# BareBonesArduino.net
KiCad netlist of a schematic drawn in EAGLE
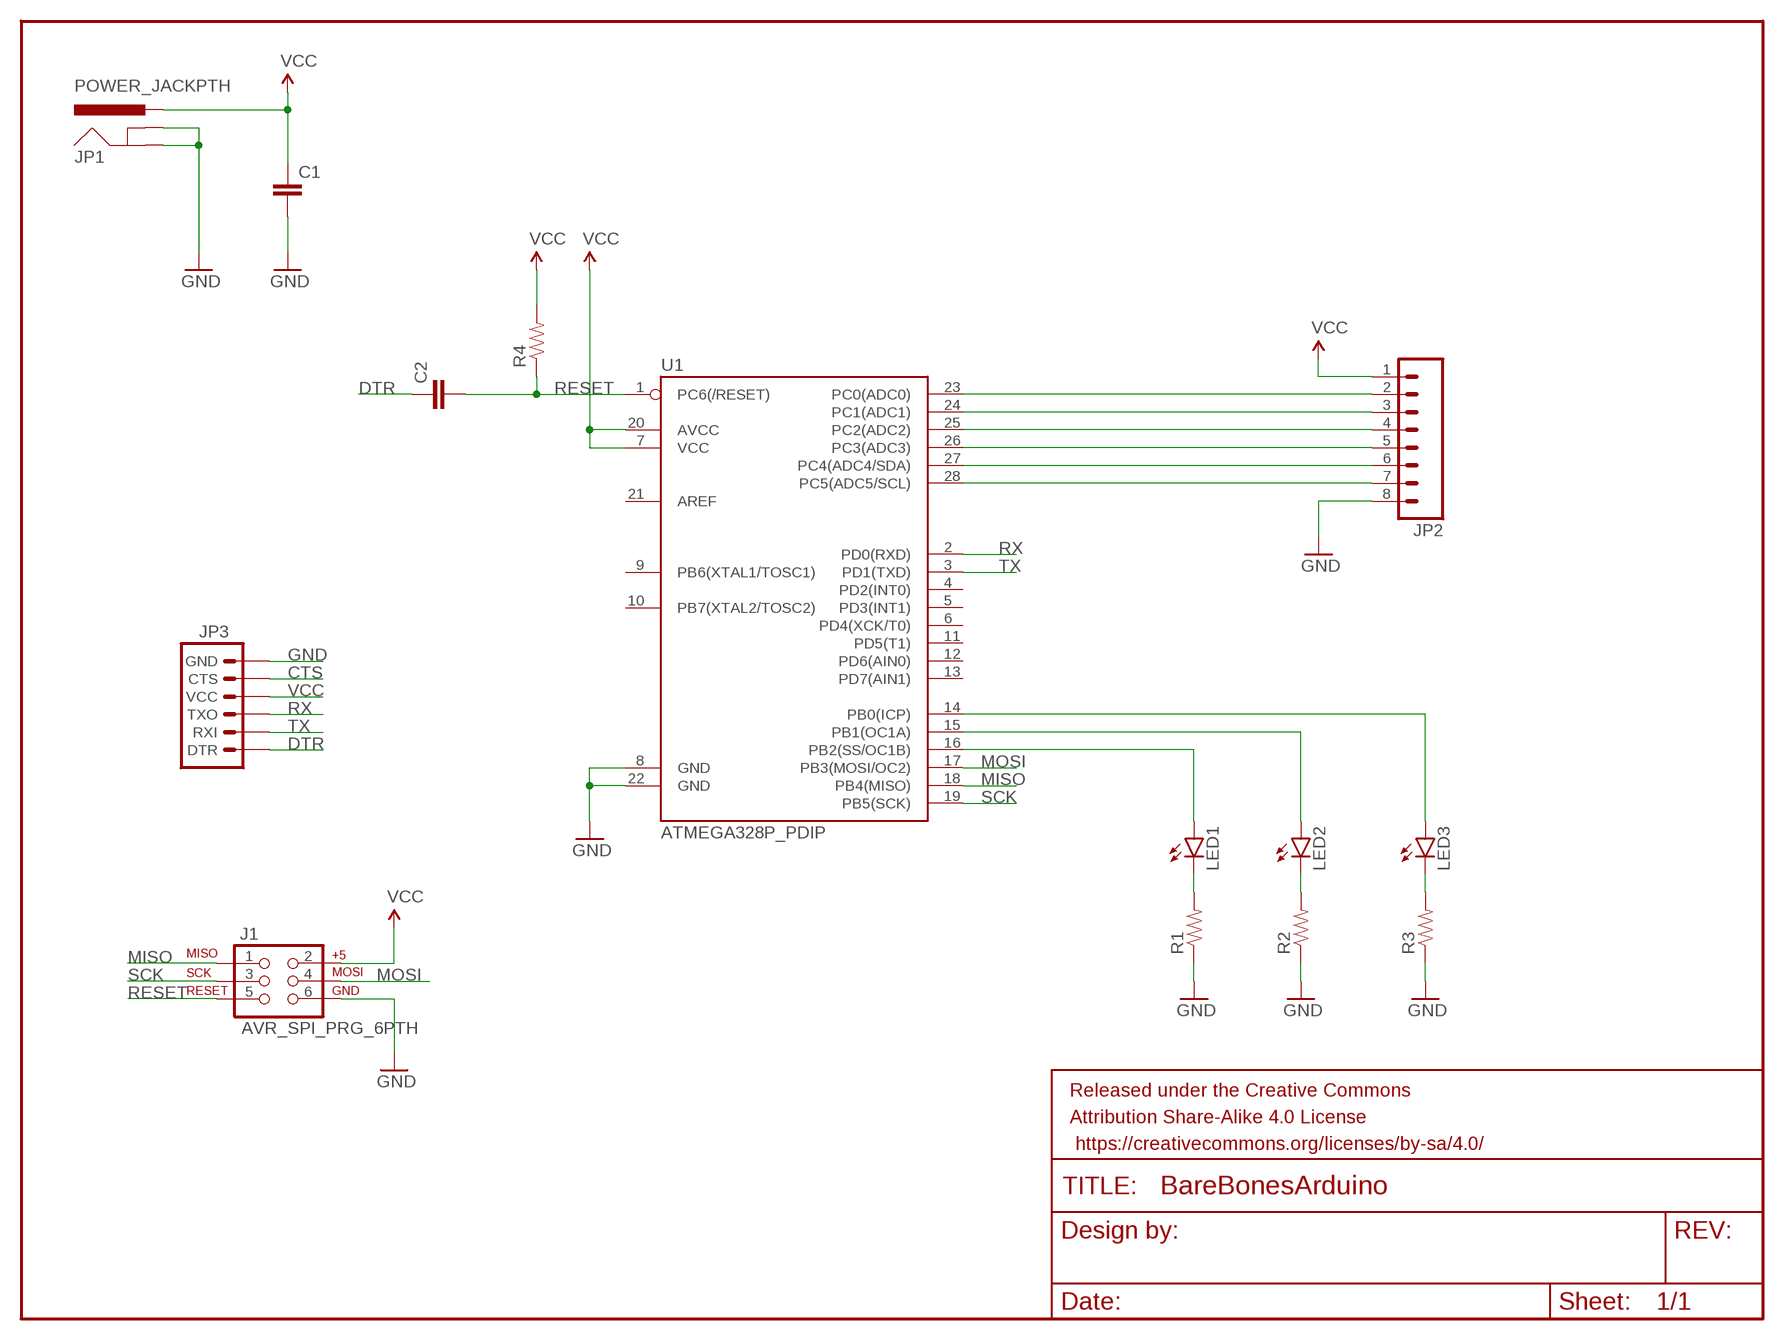
[diagram p0: schematic, sheet 1]

(export (version "E")
  (design (tool "Eeschema 10.0.6"))
  (components
    (comp (ref "C1")
      (value "CAPPTH")
      (footprint "eagle-import:CAP-PTH-SMALL")
      (libsource (lib "eagle-import") (part "CAPPTH"))
    )
    (comp (ref "C2")
      (value "CAPPTH")
      (footprint "eagle-import:CAP-PTH-SMALL")
      (libsource (lib "eagle-import") (part "CAPPTH"))
    )
    (comp (ref "FRAME1")
      (value "FRAME-LETTER")
      (footprint "eagle-import:CREATIVE_COMMONS")
      (libsource (lib "eagle-import") (part "FRAME-LETTER"))
    )
    (comp (ref "J1")
      (value "AVR_SPI_PRG_6PTH")
      (footprint "eagle-import:2X3")
      (libsource (lib "eagle-import") (part "AVR_SPI_PRG_6PTH"))
    )
    (comp (ref "JP1")
      (value "POWER_JACKPTH")
      (footprint "eagle-import:POWER_JACK_PTH")
      (libsource (lib "eagle-import") (part "POWER_JACKPTH"))
    )
    (comp (ref "JP2")
      (value "M08")
      (footprint "eagle-import:1X08_ROUND")
      (libsource (lib "eagle-import") (part "M08"))
    )
    (comp (ref "JP3")
      (value "ARDUINO_SERIAL_PROGRAMPTH")
      (footprint "eagle-import:1X06")
      (libsource (lib "eagle-import") (part "ARDUINO_SERIAL_PROGRAMPTH"))
    )
    (comp (ref "LED1")
      (value "LED5MM")
      (footprint "eagle-import:LED5MM")
      (libsource (lib "eagle-import") (part "LED5MM"))
    )
    (comp (ref "LED2")
      (value "LED5MM")
      (footprint "eagle-import:LED5MM")
      (libsource (lib "eagle-import") (part "LED5MM"))
    )
    (comp (ref "LED3")
      (value "LED5MM")
      (footprint "eagle-import:LED5MM")
      (libsource (lib "eagle-import") (part "LED5MM"))
    )
    (comp (ref "R1")
      (value "RESISTORPTH-1/4W")
      (footprint "eagle-import:AXIAL-0.4")
      (libsource (lib "eagle-import") (part "RESISTORPTH-1/4W"))
    )
    (comp (ref "R2")
      (value "RESISTORPTH-1/4W")
      (footprint "eagle-import:AXIAL-0.4")
      (libsource (lib "eagle-import") (part "RESISTORPTH-1/4W"))
    )
    (comp (ref "R3")
      (value "RESISTORPTH-1/4W")
      (footprint "eagle-import:AXIAL-0.4")
      (libsource (lib "eagle-import") (part "RESISTORPTH-1/4W"))
    )
    (comp (ref "R4")
      (value "RESISTORPTH-1/4W")
      (footprint "eagle-import:AXIAL-0.4")
      (libsource (lib "eagle-import") (part "RESISTORPTH-1/4W"))
    )
    (comp (ref "U1")
      (value "ATMEGA328P_PDIP")
      (footprint "eagle-import:DIL28-3")
      (libsource (lib "eagle-import") (part "ATMEGA328P_PDIP"))
    )
  )
  (nets
    (net (code "1") (name "/CTS") (class "Default")
      (node (ref "JP3") (pin "5") (pinfunction "CTS_5") (pintype "passive"))
    )
    (net (code "2") (name "/DTR") (class "Default")
      (node (ref "C2") (pin "1") (pinfunction "1_1") (pintype "passive"))
      (node (ref "JP3") (pin "1") (pinfunction "DTR_1") (pintype "passive"))
    )
    (net (code "3") (name "/MISO") (class "Default")
      (node (ref "J1") (pin "1") (pinfunction "1_1") (pintype "passive"))
      (node (ref "U1") (pin "18") (pinfunction "PB4(MISO)_18") (pintype "bidirectional"))
    )
    (net (code "4") (name "/MOSI") (class "Default")
      (node (ref "J1") (pin "4") (pinfunction "4_4") (pintype "passive"))
      (node (ref "U1") (pin "17") (pinfunction "PB3(MOSI/OC2)_17") (pintype "bidirectional"))
    )
    (net (code "5") (name "/RESET") (class "Default")
      (node (ref "C2") (pin "2") (pinfunction "2_2") (pintype "passive"))
      (node (ref "J1") (pin "5") (pinfunction "5_5") (pintype "passive"))
      (node (ref "R4") (pin "P$1") (pinfunction "1_P$1") (pintype "passive"))
      (node (ref "U1") (pin "1") (pinfunction "PC6(/RESET)_1") (pintype "bidirectional"))
    )
    (net (code "6") (name "/RX") (class "Default")
      (node (ref "JP3") (pin "3") (pinfunction "TXO_3") (pintype "passive"))
      (node (ref "U1") (pin "2") (pinfunction "PD0(RXD)_2") (pintype "bidirectional"))
    )
    (net (code "7") (name "/SCK") (class "Default")
      (node (ref "J1") (pin "3") (pinfunction "3_3") (pintype "passive"))
      (node (ref "U1") (pin "19") (pinfunction "PB5(SCK)_19") (pintype "bidirectional"))
    )
    (net (code "8") (name "/TX") (class "Default")
      (node (ref "JP3") (pin "2") (pinfunction "RXI_2") (pintype "passive"))
      (node (ref "U1") (pin "3") (pinfunction "PD1(TXD)_3") (pintype "bidirectional"))
    )
    (net (code "9") (name "GND") (class "Default")
      (node (ref "C1") (pin "2") (pinfunction "2_2") (pintype "passive"))
      (node (ref "J1") (pin "6") (pinfunction "6_6") (pintype "passive"))
      (node (ref "JP1") (pin "GND") (pinfunction "GND_GND") (pintype "bidirectional"))
      (node (ref "JP1") (pin "GNDBREAK") (pinfunction "GNDBREAK_GNDBREAK") (pintype "bidirectional"))
      (node (ref "JP2") (pin "8") (pinfunction "8_8") (pintype "passive"))
      (node (ref "JP3") (pin "6") (pinfunction "GND_6") (pintype "passive"))
      (node (ref "R1") (pin "P$1") (pinfunction "1_P$1") (pintype "passive"))
      (node (ref "R2") (pin "P$1") (pinfunction "1_P$1") (pintype "passive"))
      (node (ref "R3") (pin "P$1") (pinfunction "1_P$1") (pintype "passive"))
      (node (ref "U1") (pin "22") (pinfunction "GND_22") (pintype "bidirectional"))
      (node (ref "U1") (pin "8") (pinfunction "GND_8") (pintype "bidirectional"))
    )
    (net (code "10") (name "Net-(LED1-C)") (class "Default")
      (node (ref "LED1") (pin "K") (pinfunction "C_K") (pintype "passive"))
      (node (ref "R1") (pin "P$2") (pinfunction "2_P$2") (pintype "passive"))
    )
    (net (code "11") (name "Net-(LED2-C)") (class "Default")
      (node (ref "LED2") (pin "K") (pinfunction "C_K") (pintype "passive"))
      (node (ref "R2") (pin "P$2") (pinfunction "2_P$2") (pintype "passive"))
    )
    (net (code "12") (name "Net-(LED3-C)") (class "Default")
      (node (ref "LED3") (pin "K") (pinfunction "C_K") (pintype "passive"))
      (node (ref "R3") (pin "P$2") (pinfunction "2_P$2") (pintype "passive"))
    )
    (net (code "13") (name "Net-(U1-PB0(ICP))") (class "Default")
      (node (ref "LED3") (pin "A") (pinfunction "A_A") (pintype "passive"))
      (node (ref "U1") (pin "14") (pinfunction "PB0(ICP)_14") (pintype "bidirectional"))
    )
    (net (code "14") (name "Net-(U1-PB1(OC1A))") (class "Default")
      (node (ref "LED2") (pin "A") (pinfunction "A_A") (pintype "passive"))
      (node (ref "U1") (pin "15") (pinfunction "PB1(OC1A)_15") (pintype "bidirectional"))
    )
    (net (code "15") (name "Net-(U1-PB2(SS{slash}OC1B))") (class "Default")
      (node (ref "LED1") (pin "A") (pinfunction "A_A") (pintype "passive"))
      (node (ref "U1") (pin "16") (pinfunction "PB2(SS/OC1B)_16") (pintype "bidirectional"))
    )
    (net (code "16") (name "Net-(U1-PC0(ADC0))") (class "Default")
      (node (ref "JP2") (pin "2") (pinfunction "2_2") (pintype "passive"))
      (node (ref "U1") (pin "23") (pinfunction "PC0(ADC0)_23") (pintype "bidirectional"))
    )
    (net (code "17") (name "Net-(U1-PC1(ADC1))") (class "Default")
      (node (ref "JP2") (pin "3") (pinfunction "3_3") (pintype "passive"))
      (node (ref "U1") (pin "24") (pinfunction "PC1(ADC1)_24") (pintype "bidirectional"))
    )
    (net (code "18") (name "Net-(U1-PC2(ADC2))") (class "Default")
      (node (ref "JP2") (pin "4") (pinfunction "4_4") (pintype "passive"))
      (node (ref "U1") (pin "25") (pinfunction "PC2(ADC2)_25") (pintype "bidirectional"))
    )
    (net (code "19") (name "Net-(U1-PC3(ADC3))") (class "Default")
      (node (ref "JP2") (pin "5") (pinfunction "5_5") (pintype "passive"))
      (node (ref "U1") (pin "26") (pinfunction "PC3(ADC3)_26") (pintype "bidirectional"))
    )
    (net (code "20") (name "Net-(U1-PC4(ADC4{slash}SDA))") (class "Default")
      (node (ref "JP2") (pin "6") (pinfunction "6_6") (pintype "passive"))
      (node (ref "U1") (pin "27") (pinfunction "PC4(ADC4/SDA)_27") (pintype "bidirectional"))
    )
    (net (code "21") (name "Net-(U1-PC5(ADC5{slash}SCL))") (class "Default")
      (node (ref "JP2") (pin "7") (pinfunction "7_7") (pintype "passive"))
      (node (ref "U1") (pin "28") (pinfunction "PC5(ADC5/SCL)_28") (pintype "bidirectional"))
    )
    (net (code "22") (name "VCC") (class "Default")
      (node (ref "C1") (pin "1") (pinfunction "1_1") (pintype "passive"))
      (node (ref "J1") (pin "2") (pinfunction "2_2") (pintype "passive"))
      (node (ref "JP1") (pin "PWR") (pinfunction "PWR_PWR") (pintype "bidirectional"))
      (node (ref "JP2") (pin "1") (pinfunction "1_1") (pintype "passive"))
      (node (ref "JP3") (pin "4") (pinfunction "VCC_4") (pintype "passive"))
      (node (ref "R4") (pin "P$2") (pinfunction "2_P$2") (pintype "passive"))
      (node (ref "U1") (pin "20") (pinfunction "AVCC_20") (pintype "bidirectional"))
      (node (ref "U1") (pin "7") (pinfunction "VCC_7") (pintype "bidirectional"))
    )
    (net (code "23") (name "unconnected-(U1-AREF-Pad21)") (class "Default")
      (node (ref "U1") (pin "21") (pinfunction "AREF_21") (pintype "bidirectional"))
    )
    (net (code "24") (name "unconnected-(U1-PB6(XTAL1{slash}TOSC1)-Pad9)") (class "Default")
      (node (ref "U1") (pin "9") (pinfunction "PB6(XTAL1/TOSC1)_9") (pintype "bidirectional"))
    )
    (net (code "25") (name "unconnected-(U1-PB7(XTAL2{slash}TOSC2)-Pad10)") (class "Default")
      (node (ref "U1") (pin "10") (pinfunction "PB7(XTAL2/TOSC2)_10") (pintype "bidirectional"))
    )
    (net (code "26") (name "unconnected-(U1-PD2(INT0)-Pad4)") (class "Default")
      (node (ref "U1") (pin "4") (pinfunction "PD2(INT0)_4") (pintype "bidirectional"))
    )
    (net (code "27") (name "unconnected-(U1-PD3(INT1)-Pad5)") (class "Default")
      (node (ref "U1") (pin "5") (pinfunction "PD3(INT1)_5") (pintype "bidirectional"))
    )
    (net (code "28") (name "unconnected-(U1-PD4(XCK{slash}T0)-Pad6)") (class "Default")
      (node (ref "U1") (pin "6") (pinfunction "PD4(XCK/T0)_6") (pintype "bidirectional"))
    )
    (net (code "29") (name "unconnected-(U1-PD5(T1)-Pad11)") (class "Default")
      (node (ref "U1") (pin "11") (pinfunction "PD5(T1)_11") (pintype "bidirectional"))
    )
    (net (code "30") (name "unconnected-(U1-PD6(AIN0)-Pad12)") (class "Default")
      (node (ref "U1") (pin "12") (pinfunction "PD6(AIN0)_12") (pintype "bidirectional"))
    )
    (net (code "31") (name "unconnected-(U1-PD7(AIN1)-Pad13)") (class "Default")
      (node (ref "U1") (pin "13") (pinfunction "PD7(AIN1)_13") (pintype "bidirectional"))
    )
  )
)
